# DE-151116.net
KiCad netlist of a schematic drawn in Altium Designer
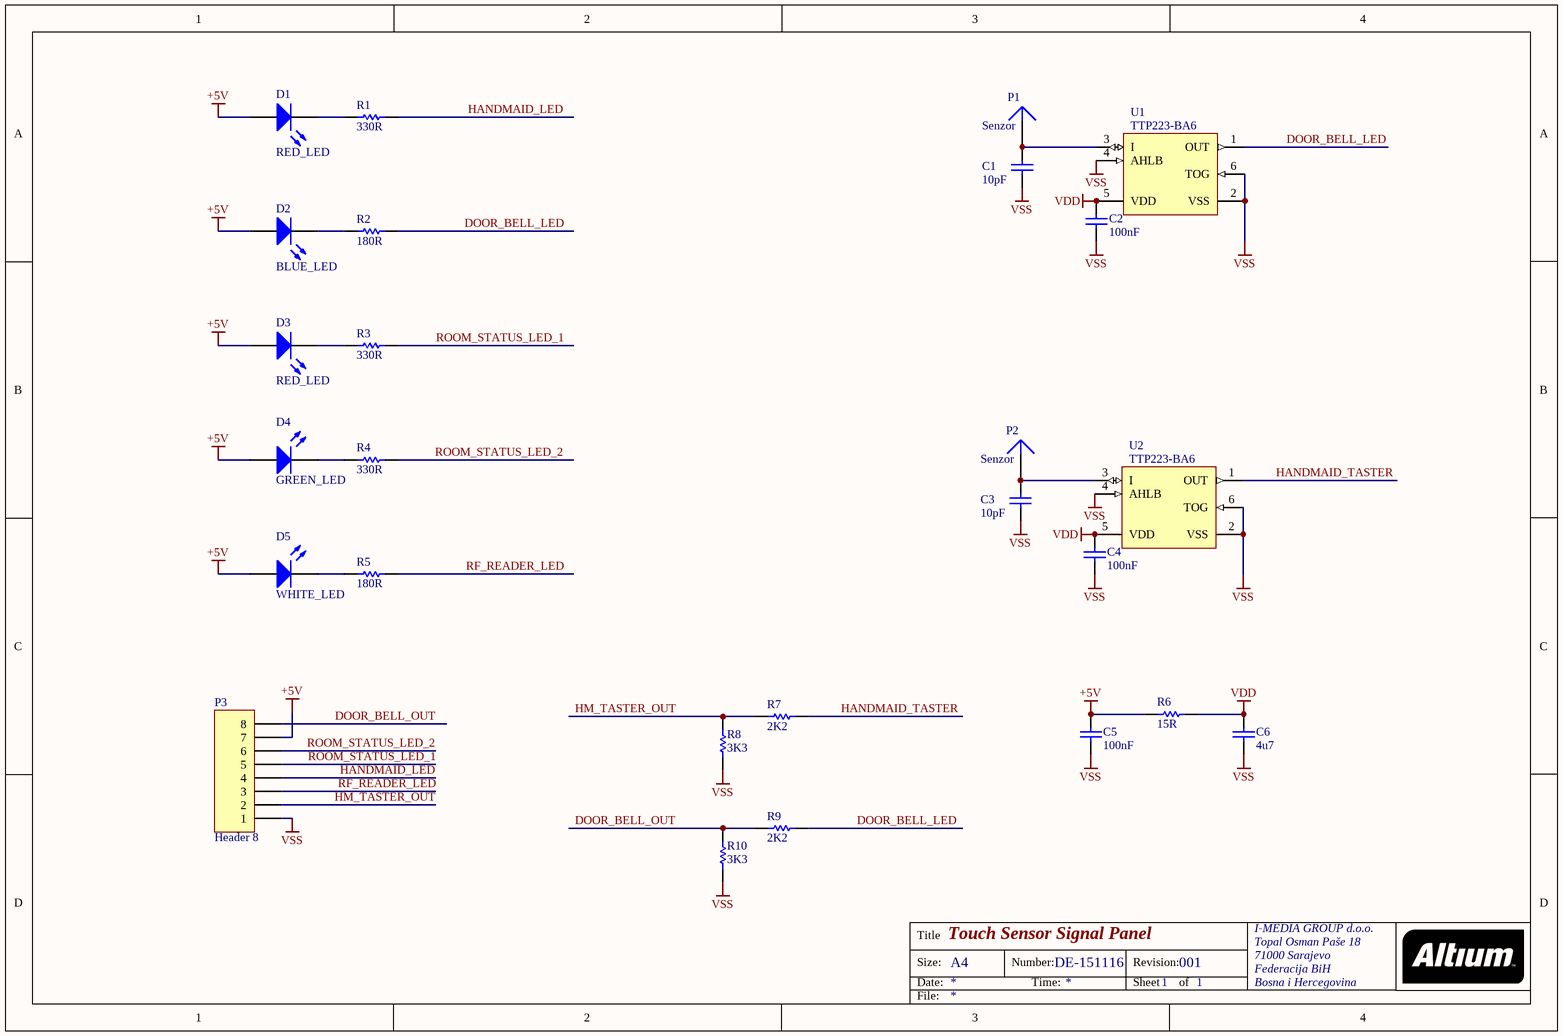
[diagram p0: DE-151116.SchDoc]

(export (version "E")
  (design (tool "Eeschema 10.0.6"))
  (components
    (comp (ref "C1")
      (value "10pF")
      (footprint "0603")
      (description "Ceramic Chip Capacitor - Standard")
      (fields (field (name "PUBLISHER") "Altium Limited"))
      (libsource (lib "KEMET Chip Capacitor") (part "C0603"))
    )
    (comp (ref "C2")
      (value "100nF")
      (footprint "0603")
      (description "Ceramic Chip Capacitor - Standard")
      (fields (field (name "PUBLISHER") "Altium Limited"))
      (libsource (lib "KEMET Chip Capacitor") (part "C0603"))
    )
    (comp (ref "C3")
      (value "10pF")
      (footprint "0603")
      (description "Ceramic Chip Capacitor - Standard")
      (fields (field (name "PUBLISHER") "Altium Limited"))
      (libsource (lib "KEMET Chip Capacitor") (part "C0603"))
    )
    (comp (ref "C4")
      (value "100nF")
      (footprint "0603")
      (description "Ceramic Chip Capacitor - Standard")
      (fields (field (name "PUBLISHER") "Altium Limited"))
      (libsource (lib "KEMET Chip Capacitor") (part "C0603"))
    )
    (comp (ref "C5")
      (value "100nF")
      (footprint "0603")
      (description "Ceramic Chip Capacitor - Standard")
      (fields (field (name "PUBLISHER") "Altium Limited"))
      (libsource (lib "KEMET Chip Capacitor") (part "C0603"))
    )
    (comp (ref "C6")
      (value "4u7")
      (footprint "0805")
      (description "Ceramic Chip Capacitor - Standard")
      (fields (field (name "PUBLISHER") "Altium Limited"))
      (libsource (lib "KEMET Chip Capacitor") (part "C0805"))
    )
    (comp (ref "D1")
      (value "RED_LED")
      (footprint "1.6X0.8X0.8")
      (description "High Performance Chip LED, Red")
      (fields (field (name "PUBLISHER") "Altium Limited"))
      (libsource (lib "Agilent Optoelectronic LED") (part "HSMC-C190"))
    )
    (comp (ref "D2")
      (value "BLUE_LED")
      (footprint "1.6X0.8X0.8")
      (description "Blue Surface Mount Chip LED, Blue")
      (fields (field (name "PUBLISHER") "Altium Limited"))
      (libsource (lib "Agilent Optoelectronic LED") (part "HSMB-C190"))
    )
    (comp (ref "D3")
      (value "RED_LED")
      (footprint "1.6X0.8X0.8")
      (description "High Performance Chip LED, Red")
      (fields (field (name "PUBLISHER") "Altium Limited"))
      (libsource (lib "Agilent Optoelectronic LED") (part "HSMC-C190"))
    )
    (comp (ref "D4")
      (value "GREEN_LED")
      (footprint "1.6X0.8X0.8")
      (description "High Performance SMT Chip LED, Green")
      (fields (field (name "PUBLISHER") "Altium Limited"))
      (libsource (lib "Agilent Optoelectronic LED") (part "HSMM-C190"))
    )
    (comp (ref "D5")
      (value "WHITE_LED")
      (footprint "1.6X0.8X0.8")
      (description "High Performance Chip LED, Amber")
      (fields (field (name "PUBLISHER") "Altium Limited"))
      (libsource (lib "Agilent Optoelectronic LED") (part "HSMA-C190"))
    )
    (comp (ref "P1")
      (value "Senzor")
      (footprint "PIN1")
      (description "Plug")
      (fields (field (name "PUBLISHER") "Altium Limited"))
      (libsource (lib "Miscellaneous Connectors") (part "Plug"))
    )
    (comp (ref "P2")
      (value "Senzor")
      (footprint "PIN1")
      (description "Plug")
      (fields (field (name "PUBLISHER") "Altium Limited"))
      (libsource (lib "Miscellaneous Connectors") (part "Plug"))
    )
    (comp (ref "P3")
      (value "Header 8")
      (footprint "HDR1X8")
      (description "Header, 8-Pin")
      (fields (field (name "PUBLISHER") "Altium Limited"))
      (libsource (lib "Miscellaneous Connectors") (part "Header 8"))
    )
    (comp (ref "R1")
      (value "330R")
      (footprint "ERA-0603")
      (fields (field (name "PUBLISHER") "Altium Limited"))
      (libsource (lib "DE-170916") (part "ERAV"))
    )
    (comp (ref "R2")
      (value "180R")
      (footprint "ERA-0603")
      (fields (field (name "PUBLISHER") "Altium Limited"))
      (libsource (lib "DE-170916") (part "ERAV"))
    )
    (comp (ref "R3")
      (value "330R")
      (footprint "ERA-0603")
      (fields (field (name "PUBLISHER") "Altium Limited"))
      (libsource (lib "DE-170916") (part "ERAV"))
    )
    (comp (ref "R4")
      (value "330R")
      (footprint "ERA-0603")
      (fields (field (name "PUBLISHER") "Altium Limited"))
      (libsource (lib "DE-170916") (part "ERAV"))
    )
    (comp (ref "R5")
      (value "180R")
      (footprint "ERA-0603")
      (fields (field (name "PUBLISHER") "Altium Limited"))
      (libsource (lib "DE-170916") (part "ERAV"))
    )
    (comp (ref "R6")
      (value "15R")
      (footprint "ERA-0805")
      (fields (field (name "PUBLISHER") "Altium Limited"))
      (libsource (lib "Panasonic Resistor") (part "ERA6Y"))
    )
    (comp (ref "R7")
      (value "2K2")
      (footprint "ERA-0603")
      (fields (field (name "PUBLISHER") "Altium Limited"))
      (libsource (lib "DE-170916") (part "ERAV"))
    )
    (comp (ref "R8")
      (value "3K3")
      (footprint "ERA-0603")
      (fields (field (name "PUBLISHER") "Altium Limited"))
      (libsource (lib "DE-170916") (part "ERAV"))
    )
    (comp (ref "R9")
      (value "2K2")
      (footprint "ERA-0603")
      (fields (field (name "PUBLISHER") "Altium Limited"))
      (libsource (lib "DE-170916") (part "ERAV"))
    )
    (comp (ref "R10")
      (value "3K3")
      (footprint "ERA-0603")
      (fields (field (name "PUBLISHER") "Altium Limited"))
      (libsource (lib "DE-170916") (part "ERAV"))
    )
    (comp (ref "U1")
      (value "TTP223-BA6")
      (footprint "6ST1_N")
      (description "One-channel Toggle-mode Touch Sensor IC with Power Management Functions, 6-pin SOT23")
      (fields (field (name "PUBLISHER") "Altium Limited"))
      (libsource (lib "Atmel Touch Solutions") (part "AT42QT1012"))
    )
    (comp (ref "U2")
      (value "TTP223-BA6")
      (footprint "6ST1_N")
      (description "One-channel Toggle-mode Touch Sensor IC with Power Management Functions, 6-pin SOT23")
      (fields (field (name "PUBLISHER") "Altium Limited"))
      (libsource (lib "Atmel Touch Solutions") (part "AT42QT1012"))
    )
  )
  (nets
    (net (code "1") (name "+5V") (class "Default")
      (node (ref "C5") (pin "2") (pinfunction "2_2") (pintype "passive"))
      (node (ref "D1") (pin "1") (pinfunction "A_1") (pintype "passive"))
      (node (ref "D2") (pin "1") (pinfunction "A_1") (pintype "passive"))
      (node (ref "D3") (pin "1") (pinfunction "A_1") (pintype "passive"))
      (node (ref "D4") (pin "1") (pinfunction "A_1") (pintype "passive"))
      (node (ref "D5") (pin "1") (pinfunction "A_1") (pintype "passive"))
      (node (ref "P3") (pin "7") (pinfunction "7_7") (pintype "passive"))
      (node (ref "R6") (pin "1") (pinfunction "1_1") (pintype "passive"))
    )
    (net (code "2") (name "/DOOR_BELL_LED") (class "Default")
      (node (ref "R2") (pin "1") (pinfunction "1_1") (pintype "passive"))
      (node (ref "R9") (pin "1") (pinfunction "1_1") (pintype "passive"))
      (node (ref "U1") (pin "1") (pinfunction "OUT_1") (pintype "output"))
    )
    (net (code "3") (name "/DOOR_BELL_OUT") (class "Default")
      (node (ref "P3") (pin "8") (pinfunction "8_8") (pintype "passive"))
      (node (ref "R10") (pin "1") (pinfunction "1_1") (pintype "passive"))
      (node (ref "R9") (pin "2") (pinfunction "2_2") (pintype "passive"))
    )
    (net (code "4") (name "/HANDMAID_LED") (class "Default")
      (node (ref "P3") (pin "4") (pinfunction "4_4") (pintype "passive"))
      (node (ref "R1") (pin "1") (pinfunction "1_1") (pintype "passive"))
    )
    (net (code "5") (name "/HANDMAID_TASTER") (class "Default")
      (node (ref "R7") (pin "1") (pinfunction "1_1") (pintype "passive"))
      (node (ref "U2") (pin "1") (pinfunction "OUT_1") (pintype "output"))
    )
    (net (code "6") (name "/HM_TASTER_OUT") (class "Default")
      (node (ref "P3") (pin "2") (pinfunction "2_2") (pintype "passive"))
      (node (ref "R7") (pin "2") (pinfunction "2_2") (pintype "passive"))
      (node (ref "R8") (pin "1") (pinfunction "1_1") (pintype "passive"))
    )
    (net (code "7") (name "/RF_READER_LED") (class "Default")
      (node (ref "P3") (pin "3") (pinfunction "3_3") (pintype "passive"))
      (node (ref "R5") (pin "1") (pinfunction "1_1") (pintype "passive"))
    )
    (net (code "8") (name "/ROOM_STATUS_LED_1") (class "Default")
      (node (ref "P3") (pin "5") (pinfunction "5_5") (pintype "passive"))
      (node (ref "R3") (pin "1") (pinfunction "1_1") (pintype "passive"))
    )
    (net (code "9") (name "/ROOM_STATUS_LED_2") (class "Default")
      (node (ref "P3") (pin "6") (pinfunction "6_6") (pintype "passive"))
      (node (ref "R4") (pin "1") (pinfunction "1_1") (pintype "passive"))
    )
    (net (code "10") (name "Net-(D1-K)") (class "Default")
      (node (ref "D1") (pin "2") (pinfunction "K_2") (pintype "passive"))
      (node (ref "R1") (pin "2") (pinfunction "2_2") (pintype "passive"))
    )
    (net (code "11") (name "Net-(D2-K)") (class "Default")
      (node (ref "D2") (pin "2") (pinfunction "K_2") (pintype "passive"))
      (node (ref "R2") (pin "2") (pinfunction "2_2") (pintype "passive"))
    )
    (net (code "12") (name "Net-(D3-K)") (class "Default")
      (node (ref "D3") (pin "2") (pinfunction "K_2") (pintype "passive"))
      (node (ref "R3") (pin "2") (pinfunction "2_2") (pintype "passive"))
    )
    (net (code "13") (name "Net-(D4-K)") (class "Default")
      (node (ref "D4") (pin "2") (pinfunction "K_2") (pintype "passive"))
      (node (ref "R4") (pin "2") (pinfunction "2_2") (pintype "passive"))
    )
    (net (code "14") (name "Net-(D5-K)") (class "Default")
      (node (ref "D5") (pin "2") (pinfunction "K_2") (pintype "passive"))
      (node (ref "R5") (pin "2") (pinfunction "2_2") (pintype "passive"))
    )
    (net (code "15") (name "Net-(U1-I)") (class "Default")
      (node (ref "C1") (pin "1") (pinfunction "1_1") (pintype "passive"))
      (node (ref "P1") (pin "1") (pinfunction "1_1") (pintype "passive"))
      (node (ref "U1") (pin "3") (pinfunction "I_3") (pintype "bidirectional"))
    )
    (net (code "16") (name "Net-(U2-I)") (class "Default")
      (node (ref "C3") (pin "1") (pinfunction "1_1") (pintype "passive"))
      (node (ref "P2") (pin "1") (pinfunction "1_1") (pintype "passive"))
      (node (ref "U2") (pin "3") (pinfunction "I_3") (pintype "bidirectional"))
    )
    (net (code "17") (name "VDD") (class "Default")
      (node (ref "C2") (pin "2") (pinfunction "2_2") (pintype "passive"))
      (node (ref "C4") (pin "2") (pinfunction "2_2") (pintype "passive"))
      (node (ref "C6") (pin "2") (pinfunction "2_2") (pintype "passive"))
      (node (ref "R6") (pin "2") (pinfunction "2_2") (pintype "passive"))
      (node (ref "U1") (pin "5") (pinfunction "VDD_5") (pintype "power_in"))
      (node (ref "U2") (pin "5") (pinfunction "VDD_5") (pintype "power_in"))
    )
    (net (code "18") (name "VSS") (class "Default")
      (node (ref "C1") (pin "2") (pinfunction "2_2") (pintype "passive"))
      (node (ref "C2") (pin "1") (pinfunction "1_1") (pintype "passive"))
      (node (ref "C3") (pin "2") (pinfunction "2_2") (pintype "passive"))
      (node (ref "C4") (pin "1") (pinfunction "1_1") (pintype "passive"))
      (node (ref "C5") (pin "1") (pinfunction "1_1") (pintype "passive"))
      (node (ref "C6") (pin "1") (pinfunction "1_1") (pintype "passive"))
      (node (ref "P3") (pin "1") (pinfunction "1_1") (pintype "passive"))
      (node (ref "R10") (pin "2") (pinfunction "2_2") (pintype "passive"))
      (node (ref "R8") (pin "2") (pinfunction "2_2") (pintype "passive"))
      (node (ref "U1") (pin "2") (pinfunction "VSS_2") (pintype "power_in"))
      (node (ref "U1") (pin "4") (pinfunction "AHLB_4") (pintype "input"))
      (node (ref "U1") (pin "6") (pinfunction "TOG_6") (pintype "input"))
      (node (ref "U2") (pin "2") (pinfunction "VSS_2") (pintype "power_in"))
      (node (ref "U2") (pin "4") (pinfunction "AHLB_4") (pintype "input"))
      (node (ref "U2") (pin "6") (pinfunction "TOG_6") (pintype "input"))
    )
  )
)
